# Roller_Ball_Lane.net
KiCad netlist of a schematic drawn in EAGLE
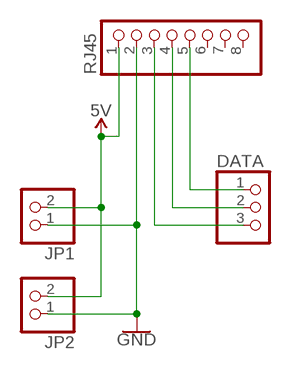
[diagram p0: schematic, sheet 1]

(export (version "E")
  (design (tool "Eeschema 10.0.6"))
  (components
    (comp (ref "DATA")
      (value "PINHD-1X3")
      (footprint "eagle-import:1X03")
      (libsource (lib "eagle-import") (part "PINHD-1X3"))
    )
    (comp (ref "JP1")
      (value "PINHD-1X2")
      (footprint "eagle-import:1X02")
      (libsource (lib "eagle-import") (part "PINHD-1X2"))
    )
    (comp (ref "JP2")
      (value "PINHD-1X2")
      (footprint "eagle-import:1X02")
      (libsource (lib "eagle-import") (part "PINHD-1X2"))
    )
    (comp (ref "RJ45")
      (value "PINHD-1X8")
      (footprint "eagle-import:1X08")
      (libsource (lib "eagle-import") (part "PINHD-1X8"))
    )
  )
  (nets
    (net (code "1") (name "5V") (class "Default")
      (node (ref "JP1") (pin "2") (pinfunction "2_2") (pintype "passive"))
      (node (ref "JP2") (pin "2") (pinfunction "2_2") (pintype "passive"))
      (node (ref "RJ45") (pin "1") (pinfunction "1_1") (pintype "passive"))
    )
    (net (code "2") (name "GND") (class "Default")
      (node (ref "JP1") (pin "1") (pinfunction "1_1") (pintype "passive"))
      (node (ref "JP2") (pin "1") (pinfunction "1_1") (pintype "passive"))
      (node (ref "RJ45") (pin "2") (pinfunction "2_2") (pintype "passive"))
    )
    (net (code "3") (name "Net-(DATA-Pad1)") (class "Default")
      (node (ref "DATA") (pin "1") (pinfunction "1_1") (pintype "passive"))
      (node (ref "RJ45") (pin "5") (pinfunction "5_5") (pintype "passive"))
    )
    (net (code "4") (name "Net-(DATA-Pad2)") (class "Default")
      (node (ref "DATA") (pin "2") (pinfunction "2_2") (pintype "passive"))
      (node (ref "RJ45") (pin "4") (pinfunction "4_4") (pintype "passive"))
    )
    (net (code "5") (name "Net-(DATA-Pad3)") (class "Default")
      (node (ref "DATA") (pin "3") (pinfunction "3_3") (pintype "passive"))
      (node (ref "RJ45") (pin "3") (pinfunction "3_3") (pintype "passive"))
    )
    (net (code "6") (name "unconnected-(RJ45-Pad6)") (class "Default")
      (node (ref "RJ45") (pin "6") (pinfunction "6_6") (pintype "passive"))
    )
    (net (code "7") (name "unconnected-(RJ45-Pad7)") (class "Default")
      (node (ref "RJ45") (pin "7") (pinfunction "7_7") (pintype "passive"))
    )
    (net (code "8") (name "unconnected-(RJ45-Pad8)") (class "Default")
      (node (ref "RJ45") (pin "8") (pinfunction "8_8") (pintype "passive"))
    )
  )
)
